# oscillator-25MHz.net
KiCad netlist of a schematic drawn in Altium Designer
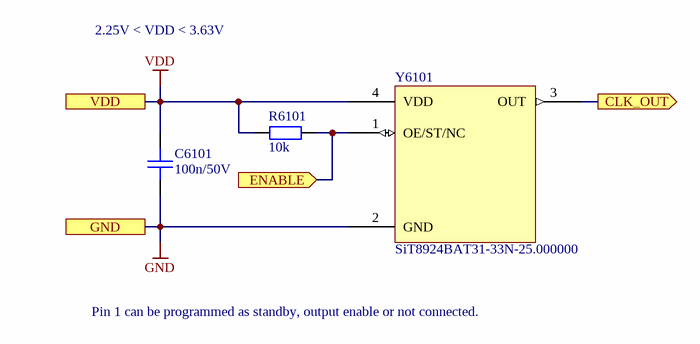
[diagram p0: oscillator-25MHz.SchDoc]

(export (version "E")
  (design (tool "Eeschema 10.0.6"))
  (components
    (comp (ref "C6101")
      (value "100n/50V")
      (footprint "CAPC1005X06N")
      (description "MLCC")
      (fields (field (name "PART NUMBER") "gen_C_ceramic_100n_50V_X7R_0402"))
      (libsource (lib "OE750") (part "C"))
    )
    (comp (ref "R6101")
      (value "10k")
      (footprint "RESC1005X04N")
      (description "SMD Resistor 10k 0402")
      (fields (field (name "PART NUMBER") "gen_R_10k_0402") (field (name "TOLERANCE") "1%"))
      (libsource (lib "OE750") (part "R"))
    )
    (comp (ref "Y6101")
      (value "SiT8924BAT31-33N-25.000000")
      (footprint "SiT8924xx-3x")
      (description "Automotive AEC-Q100 Oscillator 25MHz")
      (fields (field (name "MANUFACTURER") "SiTime"))
      (libsource (lib "OE750") (part "SiT8924"))
    )
  )
  (nets
    (net (code "1") (name "/CLK_OUT") (class "Default")
      (node (ref "Y6101") (pin "3") (pinfunction "OUT_3") (pintype "output"))
    )
    (net (code "2") (name "/ENABLE") (class "Default")
      (node (ref "R6101") (pin "2") (pinfunction "2_2") (pintype "passive"))
      (node (ref "Y6101") (pin "1") (pinfunction "OE/ST/NC_1") (pintype "bidirectional"))
    )
    (net (code "3") (name "GND") (class "Default")
      (node (ref "C6101") (pin "1") (pinfunction "1_1") (pintype "passive"))
      (node (ref "Y6101") (pin "2") (pinfunction "GND_2") (pintype "power_in"))
    )
    (net (code "4") (name "VDD") (class "Default")
      (node (ref "C6101") (pin "2") (pinfunction "2_2") (pintype "passive"))
      (node (ref "R6101") (pin "1") (pinfunction "1_1") (pintype "passive"))
      (node (ref "Y6101") (pin "4") (pinfunction "VDD_4") (pintype "power_in"))
    )
  )
)
